# FMC.net
KiCad netlist of a schematic drawn in Altium Designer
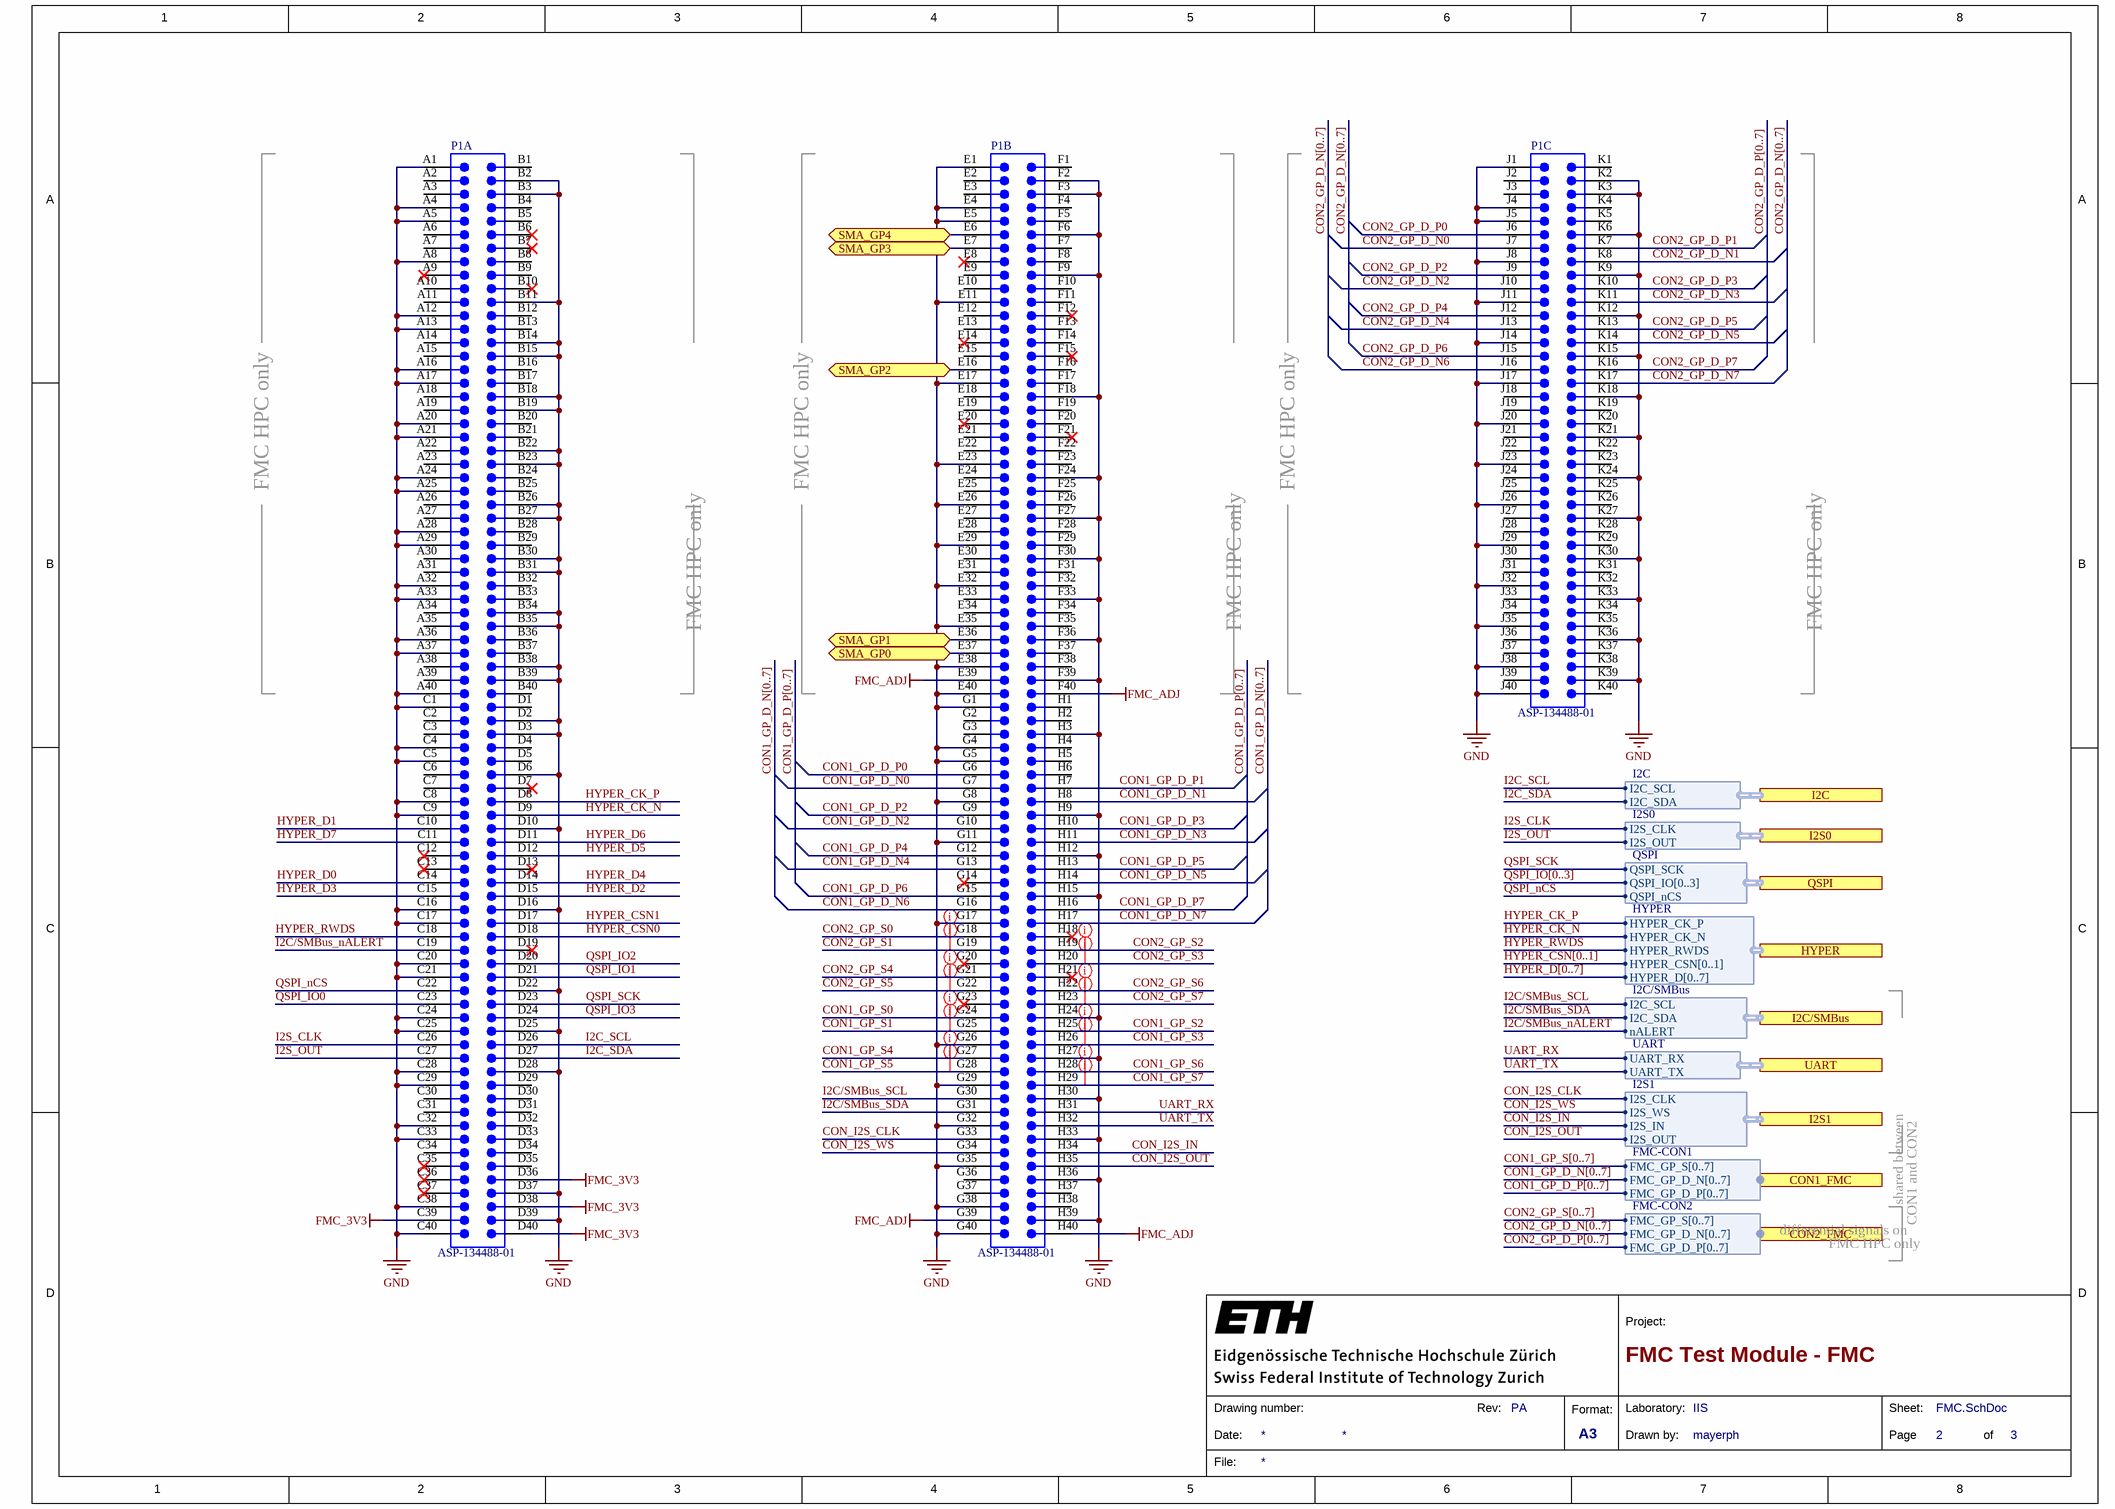
[diagram p0: FMC.SchDoc]

(export (version "E")
  (design (tool "Eeschema 10.0.6"))
  (components
    (comp (ref "P1")
      (value "ASP-134488-01")
      (footprint "BTB-SM1-27-2V400M")
      (description "Board-to-Board Connector, Vertical, 10-Row, Pitch 1.27mm, 400-Position")
      (fields (field (name "MANUFACTURER") "Samtec") (field (name "PUBLISHER") "Altium"))
      (libsource (lib "Altium Content Vault") (part "CN-2P-2M-R400"))
    )
  )
  (nets
    (net (code "11") (name "/CON1_GP_D_N0") (class "Default")
      (node (ref "P1") (pin "G7") (pinfunction "G7_G7") (pintype "passive"))
    )
    (net (code "12") (name "/CON1_GP_D_N1") (class "Default")
      (node (ref "P1") (pin "H8") (pinfunction "H8_H8") (pintype "passive"))
    )
    (net (code "13") (name "/CON1_GP_D_N2") (class "Default")
      (node (ref "P1") (pin "G10") (pinfunction "G10_G10") (pintype "passive"))
    )
    (net (code "14") (name "/CON1_GP_D_N3") (class "Default")
      (node (ref "P1") (pin "H11") (pinfunction "H11_H11") (pintype "passive"))
    )
    (net (code "15") (name "/CON1_GP_D_N4") (class "Default")
      (node (ref "P1") (pin "G13") (pinfunction "G13_G13") (pintype "passive"))
    )
    (net (code "16") (name "/CON1_GP_D_N5") (class "Default")
      (node (ref "P1") (pin "H14") (pinfunction "H14_H14") (pintype "passive"))
    )
    (net (code "17") (name "/CON1_GP_D_N6") (class "Default")
      (node (ref "P1") (pin "G16") (pinfunction "G16_G16") (pintype "passive"))
    )
    (net (code "18") (name "/CON1_GP_D_N7") (class "Default")
      (node (ref "P1") (pin "H17") (pinfunction "H17_H17") (pintype "passive"))
    )
    (net (code "20") (name "/CON1_GP_D_P0") (class "Default")
      (node (ref "P1") (pin "G6") (pinfunction "G6_G6") (pintype "passive"))
    )
    (net (code "21") (name "/CON1_GP_D_P1") (class "Default")
      (node (ref "P1") (pin "H7") (pinfunction "H7_H7") (pintype "passive"))
    )
    (net (code "22") (name "/CON1_GP_D_P2") (class "Default")
      (node (ref "P1") (pin "G9") (pinfunction "G9_G9") (pintype "passive"))
    )
    (net (code "23") (name "/CON1_GP_D_P3") (class "Default")
      (node (ref "P1") (pin "H10") (pinfunction "H10_H10") (pintype "passive"))
    )
    (net (code "24") (name "/CON1_GP_D_P4") (class "Default")
      (node (ref "P1") (pin "G12") (pinfunction "G12_G12") (pintype "passive"))
    )
    (net (code "25") (name "/CON1_GP_D_P5") (class "Default")
      (node (ref "P1") (pin "H13") (pinfunction "H13_H13") (pintype "passive"))
    )
    (net (code "26") (name "/CON1_GP_D_P6") (class "Default")
      (node (ref "P1") (pin "G15") (pinfunction "G15_G15") (pintype "passive"))
    )
    (net (code "27") (name "/CON1_GP_D_P7") (class "Default")
      (node (ref "P1") (pin "H16") (pinfunction "H16_H16") (pintype "passive"))
    )
    (net (code "29") (name "/CON1_GP_S0") (class "Default")
      (node (ref "P1") (pin "G24") (pinfunction "G24_G24") (pintype "passive"))
    )
    (net (code "30") (name "/CON1_GP_S1") (class "Default")
      (node (ref "P1") (pin "G25") (pinfunction "G25_G25") (pintype "passive"))
    )
    (net (code "31") (name "/CON1_GP_S2") (class "Default")
      (node (ref "P1") (pin "H25") (pinfunction "H25_H25") (pintype "passive"))
    )
    (net (code "32") (name "/CON1_GP_S3") (class "Default")
      (node (ref "P1") (pin "H26") (pinfunction "H26_H26") (pintype "passive"))
    )
    (net (code "33") (name "/CON1_GP_S4") (class "Default")
      (node (ref "P1") (pin "G27") (pinfunction "G27_G27") (pintype "passive"))
    )
    (net (code "34") (name "/CON1_GP_S5") (class "Default")
      (node (ref "P1") (pin "G28") (pinfunction "G28_G28") (pintype "passive"))
    )
    (net (code "35") (name "/CON1_GP_S6") (class "Default")
      (node (ref "P1") (pin "H28") (pinfunction "H28_H28") (pintype "passive"))
    )
    (net (code "36") (name "/CON1_GP_S7") (class "Default")
      (node (ref "P1") (pin "H29") (pinfunction "H29_H29") (pintype "passive"))
    )
    (net (code "39") (name "/CON2_GP_D_N0") (class "Default")
      (node (ref "P1") (pin "J7") (pinfunction "J7_J7") (pintype "passive"))
    )
    (net (code "40") (name "/CON2_GP_D_N1") (class "Default")
      (node (ref "P1") (pin "K8") (pinfunction "K8_K8") (pintype "passive"))
    )
    (net (code "41") (name "/CON2_GP_D_N2") (class "Default")
      (node (ref "P1") (pin "J10") (pinfunction "J10_J10") (pintype "passive"))
    )
    (net (code "42") (name "/CON2_GP_D_N3") (class "Default")
      (node (ref "P1") (pin "K11") (pinfunction "K11_K11") (pintype "passive"))
    )
    (net (code "43") (name "/CON2_GP_D_N4") (class "Default")
      (node (ref "P1") (pin "J13") (pinfunction "J13_J13") (pintype "passive"))
    )
    (net (code "44") (name "/CON2_GP_D_N5") (class "Default")
      (node (ref "P1") (pin "K14") (pinfunction "K14_K14") (pintype "passive"))
    )
    (net (code "45") (name "/CON2_GP_D_N6") (class "Default")
      (node (ref "P1") (pin "J16") (pinfunction "J16_J16") (pintype "passive"))
    )
    (net (code "46") (name "/CON2_GP_D_N7") (class "Default")
      (node (ref "P1") (pin "K17") (pinfunction "K17_K17") (pintype "passive"))
    )
    (net (code "48") (name "/CON2_GP_D_P0") (class "Default")
      (node (ref "P1") (pin "J6") (pinfunction "J6_J6") (pintype "passive"))
    )
    (net (code "49") (name "/CON2_GP_D_P1") (class "Default")
      (node (ref "P1") (pin "K7") (pinfunction "K7_K7") (pintype "passive"))
    )
    (net (code "50") (name "/CON2_GP_D_P2") (class "Default")
      (node (ref "P1") (pin "J9") (pinfunction "J9_J9") (pintype "passive"))
    )
    (net (code "51") (name "/CON2_GP_D_P3") (class "Default")
      (node (ref "P1") (pin "K10") (pinfunction "K10_K10") (pintype "passive"))
    )
    (net (code "52") (name "/CON2_GP_D_P4") (class "Default")
      (node (ref "P1") (pin "J12") (pinfunction "J12_J12") (pintype "passive"))
    )
    (net (code "53") (name "/CON2_GP_D_P5") (class "Default")
      (node (ref "P1") (pin "K13") (pinfunction "K13_K13") (pintype "passive"))
    )
    (net (code "54") (name "/CON2_GP_D_P6") (class "Default")
      (node (ref "P1") (pin "J15") (pinfunction "J15_J15") (pintype "passive"))
    )
    (net (code "55") (name "/CON2_GP_D_P7") (class "Default")
      (node (ref "P1") (pin "K16") (pinfunction "K16_K16") (pintype "passive"))
    )
    (net (code "57") (name "/CON2_GP_S0") (class "Default")
      (node (ref "P1") (pin "G18") (pinfunction "G18_G18") (pintype "passive"))
    )
    (net (code "58") (name "/CON2_GP_S1") (class "Default")
      (node (ref "P1") (pin "G19") (pinfunction "G19_G19") (pintype "passive"))
    )
    (net (code "59") (name "/CON2_GP_S2") (class "Default")
      (node (ref "P1") (pin "H19") (pinfunction "H19_H19") (pintype "passive"))
    )
    (net (code "60") (name "/CON2_GP_S3") (class "Default")
      (node (ref "P1") (pin "H20") (pinfunction "H20_H20") (pintype "passive"))
    )
    (net (code "61") (name "/CON2_GP_S4") (class "Default")
      (node (ref "P1") (pin "G21") (pinfunction "G21_G21") (pintype "passive"))
    )
    (net (code "62") (name "/CON2_GP_S5") (class "Default")
      (node (ref "P1") (pin "G22") (pinfunction "G22_G22") (pintype "passive"))
    )
    (net (code "63") (name "/CON2_GP_S6") (class "Default")
      (node (ref "P1") (pin "H22") (pinfunction "H22_H22") (pintype "passive"))
    )
    (net (code "64") (name "/CON2_GP_S7") (class "Default")
      (node (ref "P1") (pin "H23") (pinfunction "H23_H23") (pintype "passive"))
    )
    (net (code "66") (name "/CON_I2S_CLK") (class "Default")
      (node (ref "P1") (pin "G33") (pinfunction "G33_G33") (pintype "passive"))
    )
    (net (code "67") (name "/CON_I2S_IN") (class "Default")
      (node (ref "P1") (pin "H34") (pinfunction "H34_H34") (pintype "passive"))
    )
    (net (code "68") (name "/CON_I2S_OUT") (class "Default")
      (node (ref "P1") (pin "H35") (pinfunction "H35_H35") (pintype "passive"))
    )
    (net (code "69") (name "/CON_I2S_WS") (class "Default")
      (node (ref "P1") (pin "G34") (pinfunction "G34_G34") (pintype "passive"))
    )
    (net (code "70") (name "/HYPER_CK_N") (class "Default")
      (node (ref "P1") (pin "D9") (pinfunction "D9_D9") (pintype "passive"))
    )
    (net (code "71") (name "/HYPER_CK_P") (class "Default")
      (node (ref "P1") (pin "D8") (pinfunction "D8_D8") (pintype "passive"))
    )
    (net (code "72") (name "/HYPER_CSN0") (class "Default")
      (node (ref "P1") (pin "D18") (pinfunction "D18_D18") (pintype "passive"))
    )
    (net (code "73") (name "/HYPER_CSN1") (class "Default")
      (node (ref "P1") (pin "D17") (pinfunction "D17_D17") (pintype "passive"))
    )
    (net (code "75") (name "/HYPER_D0") (class "Default")
      (node (ref "P1") (pin "C14") (pinfunction "C14_C14") (pintype "passive"))
    )
    (net (code "76") (name "/HYPER_D1") (class "Default")
      (node (ref "P1") (pin "C10") (pinfunction "C10_C10") (pintype "passive"))
    )
    (net (code "77") (name "/HYPER_D2") (class "Default")
      (node (ref "P1") (pin "D15") (pinfunction "D15_D15") (pintype "passive"))
    )
    (net (code "78") (name "/HYPER_D3") (class "Default")
      (node (ref "P1") (pin "C15") (pinfunction "C15_C15") (pintype "passive"))
    )
    (net (code "79") (name "/HYPER_D4") (class "Default")
      (node (ref "P1") (pin "D14") (pinfunction "D14_D14") (pintype "passive"))
    )
    (net (code "80") (name "/HYPER_D5") (class "Default")
      (node (ref "P1") (pin "D12") (pinfunction "D12_D12") (pintype "passive"))
    )
    (net (code "81") (name "/HYPER_D6") (class "Default")
      (node (ref "P1") (pin "D11") (pinfunction "D11_D11") (pintype "passive"))
    )
    (net (code "82") (name "/HYPER_D7") (class "Default")
      (node (ref "P1") (pin "C11") (pinfunction "C11_C11") (pintype "passive"))
    )
    (net (code "84") (name "/HYPER_RWDS") (class "Default")
      (node (ref "P1") (pin "C18") (pinfunction "C18_C18") (pintype "passive"))
    )
    (net (code "85") (name "/I2C_SCL") (class "Default")
      (node (ref "P1") (pin "D26") (pinfunction "D26_D26") (pintype "passive"))
    )
    (net (code "86") (name "/I2C_SDA") (class "Default")
      (node (ref "P1") (pin "D27") (pinfunction "D27_D27") (pintype "passive"))
    )
    (net (code "87") (name "/I2C{slash}SMBus_SCL") (class "Default")
      (node (ref "P1") (pin "G30") (pinfunction "G30_G30") (pintype "passive"))
    )
    (net (code "88") (name "/I2C{slash}SMBus_SDA") (class "Default")
      (node (ref "P1") (pin "G31") (pinfunction "G31_G31") (pintype "passive"))
    )
    (net (code "89") (name "/I2C{slash}SMBus_nALERT") (class "Default")
      (node (ref "P1") (pin "C19") (pinfunction "C19_C19") (pintype "passive"))
    )
    (net (code "90") (name "/I2S_CLK") (class "Default")
      (node (ref "P1") (pin "C26") (pinfunction "C26_C26") (pintype "passive"))
    )
    (net (code "91") (name "/I2S_OUT") (class "Default")
      (node (ref "P1") (pin "C27") (pinfunction "C27_C27") (pintype "passive"))
    )
    (net (code "92") (name "/QSPI_IO0") (class "Default")
      (node (ref "P1") (pin "C23") (pinfunction "C23_C23") (pintype "passive"))
    )
    (net (code "93") (name "/QSPI_IO1") (class "Default")
      (node (ref "P1") (pin "D21") (pinfunction "D21_D21") (pintype "passive"))
    )
    (net (code "94") (name "/QSPI_IO2") (class "Default")
      (node (ref "P1") (pin "D20") (pinfunction "D20_D20") (pintype "passive"))
    )
    (net (code "95") (name "/QSPI_IO3") (class "Default")
      (node (ref "P1") (pin "D24") (pinfunction "D24_D24") (pintype "passive"))
    )
    (net (code "97") (name "/QSPI_SCK") (class "Default")
      (node (ref "P1") (pin "D23") (pinfunction "D23_D23") (pintype "passive"))
    )
    (net (code "98") (name "/QSPI_nCS") (class "Default")
      (node (ref "P1") (pin "C22") (pinfunction "C22_C22") (pintype "passive"))
    )
    (net (code "99") (name "/SMA_GP0") (class "Default")
      (node (ref "P1") (pin "E37") (pinfunction "E37_E37") (pintype "passive"))
    )
    (net (code "100") (name "/SMA_GP1") (class "Default")
      (node (ref "P1") (pin "E36") (pinfunction "E36_E36") (pintype "passive"))
    )
    (net (code "101") (name "/SMA_GP2") (class "Default")
      (node (ref "P1") (pin "E16") (pinfunction "E16_E16") (pintype "passive"))
    )
    (net (code "102") (name "/SMA_GP3") (class "Default")
      (node (ref "P1") (pin "E7") (pinfunction "E7_E7") (pintype "passive"))
    )
    (net (code "103") (name "/SMA_GP4") (class "Default")
      (node (ref "P1") (pin "E6") (pinfunction "E6_E6") (pintype "passive"))
    )
    (net (code "104") (name "/UART_RX") (class "Default")
      (node (ref "P1") (pin "H31") (pinfunction "H31_H31") (pintype "passive"))
    )
    (net (code "105") (name "/UART_TX") (class "Default")
      (node (ref "P1") (pin "H32") (pinfunction "H32_H32") (pintype "passive"))
    )
    (net (code "113") (name "FMC_3V3") (class "Default")
      (node (ref "P1") (pin "C39") (pinfunction "C39_C39") (pintype "passive"))
      (node (ref "P1") (pin "D36") (pinfunction "D36_D36") (pintype "passive"))
      (node (ref "P1") (pin "D38") (pinfunction "D38_D38") (pintype "passive"))
      (node (ref "P1") (pin "D40") (pinfunction "D40_D40") (pintype "passive"))
    )
    (net (code "114") (name "FMC_ADJ") (class "Default")
      (node (ref "P1") (pin "E39") (pinfunction "E39_E39") (pintype "passive"))
      (node (ref "P1") (pin "F40") (pinfunction "F40_F40") (pintype "passive"))
      (node (ref "P1") (pin "G39") (pinfunction "G39_G39") (pintype "passive"))
      (node (ref "P1") (pin "H40") (pinfunction "H40_H40") (pintype "passive"))
    )
    (net (code "115") (name "GND") (class "Default")
      (node (ref "P1") (pin "A1") (pinfunction "A1_A1") (pintype "passive"))
      (node (ref "P1") (pin "A12") (pinfunction "A12_A12") (pintype "passive"))
      (node (ref "P1") (pin "A13") (pinfunction "A13_A13") (pintype "passive"))
      (node (ref "P1") (pin "A16") (pinfunction "A16_A16") (pintype "passive"))
      (node (ref "P1") (pin "A17") (pinfunction "A17_A17") (pintype "passive"))
      (node (ref "P1") (pin "A20") (pinfunction "A20_A20") (pintype "passive"))
      (node (ref "P1") (pin "A21") (pinfunction "A21_A21") (pintype "passive"))
      (node (ref "P1") (pin "A24") (pinfunction "A24_A24") (pintype "passive"))
      (node (ref "P1") (pin "A25") (pinfunction "A25_A25") (pintype "passive"))
      (node (ref "P1") (pin "A28") (pinfunction "A28_A28") (pintype "passive"))
      (node (ref "P1") (pin "A29") (pinfunction "A29_A29") (pintype "passive"))
      (node (ref "P1") (pin "A32") (pinfunction "A32_A32") (pintype "passive"))
      (node (ref "P1") (pin "A33") (pinfunction "A33_A33") (pintype "passive"))
      (node (ref "P1") (pin "A36") (pinfunction "A36_A36") (pintype "passive"))
      (node (ref "P1") (pin "A37") (pinfunction "A37_A37") (pintype "passive"))
      (node (ref "P1") (pin "A4") (pinfunction "A4_A4") (pintype "passive"))
      (node (ref "P1") (pin "A40") (pinfunction "A40_A40") (pintype "passive"))
      (node (ref "P1") (pin "A5") (pinfunction "A5_A5") (pintype "passive"))
      (node (ref "P1") (pin "A8") (pinfunction "A8_A8") (pintype "passive"))
      (node (ref "P1") (pin "B11") (pinfunction "B11_B11") (pintype "passive"))
      (node (ref "P1") (pin "B14") (pinfunction "B14_B14") (pintype "passive"))
      (node (ref "P1") (pin "B15") (pinfunction "B15_B15") (pintype "passive"))
      (node (ref "P1") (pin "B18") (pinfunction "B18_B18") (pintype "passive"))
      (node (ref "P1") (pin "B19") (pinfunction "B19_B19") (pintype "passive"))
      (node (ref "P1") (pin "B2") (pinfunction "B2_B2") (pintype "passive"))
      (node (ref "P1") (pin "B22") (pinfunction "B22_B22") (pintype "passive"))
      (node (ref "P1") (pin "B23") (pinfunction "B23_B23") (pintype "passive"))
      (node (ref "P1") (pin "B26") (pinfunction "B26_B26") (pintype "passive"))
      (node (ref "P1") (pin "B27") (pinfunction "B27_B27") (pintype "passive"))
      (node (ref "P1") (pin "B3") (pinfunction "B3_B3") (pintype "passive"))
      (node (ref "P1") (pin "B30") (pinfunction "B30_B30") (pintype "passive"))
      (node (ref "P1") (pin "B31") (pinfunction "B31_B31") (pintype "passive"))
      (node (ref "P1") (pin "B34") (pinfunction "B34_B34") (pintype "passive"))
      (node (ref "P1") (pin "B35") (pinfunction "B35_B35") (pintype "passive"))
      (node (ref "P1") (pin "B38") (pinfunction "B38_B38") (pintype "passive"))
      (node (ref "P1") (pin "B39") (pinfunction "B39_B39") (pintype "passive"))
      (node (ref "P1") (pin "C1") (pinfunction "C1_C1") (pintype "passive"))
      (node (ref "P1") (pin "C16") (pinfunction "C16_C16") (pintype "passive"))
      (node (ref "P1") (pin "C17") (pinfunction "C17_C17") (pintype "passive"))
      (node (ref "P1") (pin "C20") (pinfunction "C20_C20") (pintype "passive"))
      (node (ref "P1") (pin "C21") (pinfunction "C21_C21") (pintype "passive"))
      (node (ref "P1") (pin "C24") (pinfunction "C24_C24") (pintype "passive"))
      (node (ref "P1") (pin "C25") (pinfunction "C25_C25") (pintype "passive"))
      (node (ref "P1") (pin "C28") (pinfunction "C28_C28") (pintype "passive"))
      (node (ref "P1") (pin "C29") (pinfunction "C29_C29") (pintype "passive"))
      (node (ref "P1") (pin "C32") (pinfunction "C32_C32") (pintype "passive"))
      (node (ref "P1") (pin "C33") (pinfunction "C33_C33") (pintype "passive"))
      (node (ref "P1") (pin "C38") (pinfunction "C38_C38") (pintype "passive"))
      (node (ref "P1") (pin "C4") (pinfunction "C4_C4") (pintype "passive"))
      (node (ref "P1") (pin "C40") (pinfunction "C40_C40") (pintype "passive"))
      (node (ref "P1") (pin "C5") (pinfunction "C5_C5") (pintype "passive"))
      (node (ref "P1") (pin "C8") (pinfunction "C8_C8") (pintype "passive"))
      (node (ref "P1") (pin "C9") (pinfunction "C9_C9") (pintype "passive"))
      (node (ref "P1") (pin "D10") (pinfunction "D10_D10") (pintype "passive"))
      (node (ref "P1") (pin "D16") (pinfunction "D16_D16") (pintype "passive"))
      (node (ref "P1") (pin "D2") (pinfunction "D2_D2") (pintype "passive"))
      (node (ref "P1") (pin "D22") (pinfunction "D22_D22") (pintype "passive"))
      (node (ref "P1") (pin "D25") (pinfunction "D25_D25") (pintype "passive"))
      (node (ref "P1") (pin "D28") (pinfunction "D28_D28") (pintype "passive"))
      (node (ref "P1") (pin "D3") (pinfunction "D3_D3") (pintype "passive"))
      (node (ref "P1") (pin "D37") (pinfunction "D37_D37") (pintype "passive"))
      (node (ref "P1") (pin "D39") (pinfunction "D39_D39") (pintype "passive"))
      (node (ref "P1") (pin "D6") (pinfunction "D6_D6") (pintype "passive"))
      (node (ref "P1") (pin "E1") (pinfunction "E1_E1") (pintype "passive"))
      (node (ref "P1") (pin "E11") (pinfunction "E11_E11") (pintype "passive"))
      (node (ref "P1") (pin "E17") (pinfunction "E17_E17") (pintype "passive"))
      (node (ref "P1") (pin "E23") (pinfunction "E23_E23") (pintype "passive"))
      (node (ref "P1") (pin "E26") (pinfunction "E26_E26") (pintype "passive"))
      (node (ref "P1") (pin "E29") (pinfunction "E29_E29") (pintype "passive"))
      (node (ref "P1") (pin "E32") (pinfunction "E32_E32") (pintype "passive"))
      (node (ref "P1") (pin "E35") (pinfunction "E35_E35") (pintype "passive"))
      (node (ref "P1") (pin "E38") (pinfunction "E38_E38") (pintype "passive"))
      (node (ref "P1") (pin "E4") (pinfunction "E4_E4") (pintype "passive"))
      (node (ref "P1") (pin "E40") (pinfunction "E40_E40") (pintype "passive"))
      (node (ref "P1") (pin "E5") (pinfunction "E5_E5") (pintype "passive"))
      (node (ref "P1") (pin "F18") (pinfunction "F18_F18") (pintype "passive"))
      (node (ref "P1") (pin "F2") (pinfunction "F2_F2") (pintype "passive"))
      (node (ref "P1") (pin "F24") (pinfunction "F24_F24") (pintype "passive"))
      (node (ref "P1") (pin "F27") (pinfunction "F27_F27") (pintype "passive"))
      (node (ref "P1") (pin "F3") (pinfunction "F3_F3") (pintype "passive"))
      (node (ref "P1") (pin "F30") (pinfunction "F30_F30") (pintype "passive"))
      (node (ref "P1") (pin "F33") (pinfunction "F33_F33") (pintype "passive"))
      (node (ref "P1") (pin "F36") (pinfunction "F36_F36") (pintype "passive"))
      (node (ref "P1") (pin "F39") (pinfunction "F39_F39") (pintype "passive"))
      (node (ref "P1") (pin "F6") (pinfunction "F6_F6") (pintype "passive"))
      (node (ref "P1") (pin "F9") (pinfunction "F9_F9") (pintype "passive"))
      (node (ref "P1") (pin "G1") (pinfunction "G1_G1") (pintype "passive"))
      (node (ref "P1") (pin "G11") (pinfunction "G11_G11") (pintype "passive"))
      (node (ref "P1") (pin "G17") (pinfunction "G17_G17") (pintype "passive"))
      (node (ref "P1") (pin "G26") (pinfunction "G26_G26") (pintype "passive"))
      (node (ref "P1") (pin "G29") (pinfunction "G29_G29") (pintype "passive"))
      (node (ref "P1") (pin "G32") (pinfunction "G32_G32") (pintype "passive"))
      (node (ref "P1") (pin "G35") (pinfunction "G35_G35") (pintype "passive"))
      (node (ref "P1") (pin "G38") (pinfunction "G38_G38") (pintype "passive"))
      (node (ref "P1") (pin "G4") (pinfunction "G4_G4") (pintype "passive"))
      (node (ref "P1") (pin "G40") (pinfunction "G40_G40") (pintype "passive"))
      (node (ref "P1") (pin "G5") (pinfunction "G5_G5") (pintype "passive"))
      (node (ref "P1") (pin "G8") (pinfunction "G8_G8") (pintype "passive"))
      (node (ref "P1") (pin "H12") (pinfunction "H12_H12") (pintype "passive"))
      (node (ref "P1") (pin "H15") (pinfunction "H15_H15") (pintype "passive"))
      (node (ref "P1") (pin "H24") (pinfunction "H24_H24") (pintype "passive"))
      (node (ref "P1") (pin "H27") (pinfunction "H27_H27") (pintype "passive"))
      (node (ref "P1") (pin "H3") (pinfunction "H3_H3") (pintype "passive"))
      (node (ref "P1") (pin "H30") (pinfunction "H30_H30") (pintype "passive"))
      (node (ref "P1") (pin "H33") (pinfunction "H33_H33") (pintype "passive"))
      (node (ref "P1") (pin "H36") (pinfunction "H36_H36") (pintype "passive"))
      (node (ref "P1") (pin "H39") (pinfunction "H39_H39") (pintype "passive"))
      (node (ref "P1") (pin "H9") (pinfunction "H9_H9") (pintype "passive"))
      (node (ref "P1") (pin "J1") (pinfunction "J1_J1") (pintype "passive"))
      (node (ref "P1") (pin "J11") (pinfunction "J11_J11") (pintype "passive"))
      (node (ref "P1") (pin "J14") (pinfunction "J14_J14") (pintype "passive"))
      (node (ref "P1") (pin "J17") (pinfunction "J17_J17") (pintype "passive"))
      (node (ref "P1") (pin "J20") (pinfunction "J20_J20") (pintype "passive"))
      (node (ref "P1") (pin "J23") (pinfunction "J23_J23") (pintype "passive"))
      (node (ref "P1") (pin "J26") (pinfunction "J26_J26") (pintype "passive"))
      (node (ref "P1") (pin "J29") (pinfunction "J29_J29") (pintype "passive"))
      (node (ref "P1") (pin "J32") (pinfunction "J32_J32") (pintype "passive"))
      (node (ref "P1") (pin "J35") (pinfunction "J35_J35") (pintype "passive"))
      (node (ref "P1") (pin "J38") (pinfunction "J38_J38") (pintype "passive"))
      (node (ref "P1") (pin "J4") (pinfunction "J4_J4") (pintype "passive"))
      (node (ref "P1") (pin "J40") (pinfunction "J40_J40") (pintype "passive"))
      (node (ref "P1") (pin "J5") (pinfunction "J5_J5") (pintype "passive"))
      (node (ref "P1") (pin "J8") (pinfunction "J8_J8") (pintype "passive"))
      (node (ref "P1") (pin "K12") (pinfunction "K12_K12") (pintype "passive"))
      (node (ref "P1") (pin "K15") (pinfunction "K15_K15") (pintype "passive"))
      (node (ref "P1") (pin "K18") (pinfunction "K18_K18") (pintype "passive"))
      (node (ref "P1") (pin "K2") (pinfunction "K2_K2") (pintype "passive"))
      (node (ref "P1") (pin "K21") (pinfunction "K21_K21") (pintype "passive"))
      (node (ref "P1") (pin "K24") (pinfunction "K24_K24") (pintype "passive"))
      (node (ref "P1") (pin "K27") (pinfunction "K27_K27") (pintype "passive"))
      (node (ref "P1") (pin "K3") (pinfunction "K3_K3") (pintype "passive"))
      (node (ref "P1") (pin "K30") (pinfunction "K30_K30") (pintype "passive"))
      (node (ref "P1") (pin "K33") (pinfunction "K33_K33") (pintype "passive"))
      (node (ref "P1") (pin "K36") (pinfunction "K36_K36") (pintype "passive"))
      (node (ref "P1") (pin "K39") (pinfunction "K39_K39") (pintype "passive"))
      (node (ref "P1") (pin "K6") (pinfunction "K6_K6") (pintype "passive"))
      (node (ref "P1") (pin "K9") (pinfunction "K9_K9") (pintype "passive"))
    )
    (net (code "116") (name "unconnected-(P1-PadA2)") (class "Default")
      (node (ref "P1") (pin "A2") (pinfunction "A2_A2") (pintype "passive"))
    )
    (net (code "117") (name "unconnected-(P1-PadA3)") (class "Default")
      (node (ref "P1") (pin "A3") (pinfunction "A3_A3") (pintype "passive"))
    )
    (net (code "118") (name "unconnected-(P1-PadA6)") (class "Default")
      (node (ref "P1") (pin "A6") (pinfunction "A6_A6") (pintype "passive"))
    )
    (net (code "119") (name "unconnected-(P1-PadA7)") (class "Default")
      (node (ref "P1") (pin "A7") (pinfunction "A7_A7") (pintype "passive"))
    )
    (net (code "120") (name "unconnected-(P1-PadA9)") (class "Default")
      (node (ref "P1") (pin "A9") (pinfunction "A9_A9") (pintype "passive+no_connect"))
    )
    (net (code "121") (name "unconnected-(P1-PadA10)") (class "Default")
      (node (ref "P1") (pin "A10") (pinfunction "A10_A10") (pintype "passive"))
    )
    (net (code "122") (name "unconnected-(P1-PadA11)") (class "Default")
      (node (ref "P1") (pin "A11") (pinfunction "A11_A11") (pintype "passive"))
    )
    (net (code "123") (name "unconnected-(P1-PadA14)") (class "Default")
      (node (ref "P1") (pin "A14") (pinfunction "A14_A14") (pintype "passive"))
    )
    (net (code "124") (name "unconnected-(P1-PadA15)") (class "Default")
      (node (ref "P1") (pin "A15") (pinfunction "A15_A15") (pintype "passive"))
    )
    (net (code "125") (name "unconnected-(P1-PadA18)") (class "Default")
      (node (ref "P1") (pin "A18") (pinfunction "A18_A18") (pintype "passive"))
    )
    (net (code "126") (name "unconnected-(P1-PadA19)") (class "Default")
      (node (ref "P1") (pin "A19") (pinfunction "A19_A19") (pintype "passive"))
    )
    (net (code "127") (name "unconnected-(P1-PadA22)") (class "Default")
      (node (ref "P1") (pin "A22") (pinfunction "A22_A22") (pintype "passive"))
    )
    (net (code "128") (name "unconnected-(P1-PadA23)") (class "Default")
      (node (ref "P1") (pin "A23") (pinfunction "A23_A23") (pintype "passive"))
    )
    (net (code "129") (name "unconnected-(P1-PadA26)") (class "Default")
      (node (ref "P1") (pin "A26") (pinfunction "A26_A26") (pintype "passive"))
    )
    (net (code "130") (name "unconnected-(P1-PadA27)") (class "Default")
      (node (ref "P1") (pin "A27") (pinfunction "A27_A27") (pintype "passive"))
    )
    (net (code "131") (name "unconnected-(P1-PadA30)") (class "Default")
      (node (ref "P1") (pin "A30") (pinfunction "A30_A30") (pintype "passive"))
    )
    (net (code "132") (name "unconnected-(P1-PadA31)") (class "Default")
      (node (ref "P1") (pin "A31") (pinfunction "A31_A31") (pintype "passive"))
    )
    (net (code "133") (name "unconnected-(P1-PadA34)") (class "Default")
      (node (ref "P1") (pin "A34") (pinfunction "A34_A34") (pintype "passive"))
    )
    (net (code "134") (name "unconnected-(P1-PadA35)") (class "Default")
      (node (ref "P1") (pin "A35") (pinfunction "A35_A35") (pintype "passive"))
    )
    (net (code "135") (name "unconnected-(P1-PadA38)") (class "Default")
      (node (ref "P1") (pin "A38") (pinfunction "A38_A38") (pintype "passive"))
    )
    (net (code "136") (name "unconnected-(P1-PadA39)") (class "Default")
      (node (ref "P1") (pin "A39") (pinfunction "A39_A39") (pintype "passive"))
    )
    (net (code "137") (name "unconnected-(P1-PadB1)") (class "Default")
      (node (ref "P1") (pin "B1") (pinfunction "B1_B1") (pintype "passive"))
    )
    (net (code "138") (name "unconnected-(P1-PadB4)") (class "Default")
      (node (ref "P1") (pin "B4") (pinfunction "B4_B4") (pintype "passive"))
    )
    (net (code "139") (name "unconnected-(P1-PadB5)") (class "Default")
      (node (ref "P1") (pin "B5") (pinfunction "B5_B5") (pintype "passive"))
    )
    (net (code "140") (name "unconnected-(P1-PadB6)") (class "Default")
      (node (ref "P1") (pin "B6") (pinfunction "B6_B6") (pintype "passive+no_connect"))
    )
    (net (code "141") (name "unconnected-(P1-PadB7)") (class "Default")
      (node (ref "P1") (pin "B7") (pinfunction "B7_B7") (pintype "passive+no_connect"))
    )
    (net (code "142") (name "unconnected-(P1-PadB8)") (class "Default")
      (node (ref "P1") (pin "B8") (pinfunction "B8_B8") (pintype "passive"))
    )
    (net (code "143") (name "unconnected-(P1-PadB9)") (class "Default")
      (node (ref "P1") (pin "B9") (pinfunction "B9_B9") (pintype "passive"))
    )
    (net (code "144") (name "unconnected-(P1-PadB10)") (class "Default")
      (node (ref "P1") (pin "B10") (pinfunction "B10_B10") (pintype "passive+no_connect"))
    )
    (net (code "145") (name "unconnected-(P1-PadB12)") (class "Default")
      (node (ref "P1") (pin "B12") (pinfunction "B12_B12") (pintype "passive"))
    )
    (net (code "146") (name "unconnected-(P1-PadB13)") (class "Default")
      (node (ref "P1") (pin "B13") (pinfunction "B13_B13") (pintype "passive"))
    )
    (net (code "147") (name "unconnected-(P1-PadB16)") (class "Default")
      (node (ref "P1") (pin "B16") (pinfunction "B16_B16") (pintype "passive"))
    )
    (net (code "148") (name "unconnected-(P1-PadB17)") (class "Default")
      (node (ref "P1") (pin "B17") (pinfunction "B17_B17") (pintype "passive"))
    )
    (net (code "149") (name "unconnected-(P1-PadB20)") (class "Default")
      (node (ref "P1") (pin "B20") (pinfunction "B20_B20") (pintype "passive"))
    )
    (net (code "150") (name "unconnected-(P1-PadB21)") (class "Default")
      (node (ref "P1") (pin "B21") (pinfunction "B21_B21") (pintype "passive"))
    )
    (net (code "151") (name "unconnected-(P1-PadB24)") (class "Default")
      (node (ref "P1") (pin "B24") (pinfunction "B24_B24") (pintype "passive"))
    )
    (net (code "152") (name "unconnected-(P1-PadB25)") (class "Default")
      (node (ref "P1") (pin "B25") (pinfunction "B25_B25") (pintype "passive"))
    )
    (net (code "153") (name "unconnected-(P1-PadB28)") (class "Default")
      (node (ref "P1") (pin "B28") (pinfunction "B28_B28") (pintype "passive"))
    )
    (net (code "154") (name "unconnected-(P1-PadB29)") (class "Default")
      (node (ref "P1") (pin "B29") (pinfunction "B29_B29") (pintype "passive"))
    )
    (net (code "155") (name "unconnected-(P1-PadB32)") (class "Default")
      (node (ref "P1") (pin "B32") (pinfunction "B32_B32") (pintype "passive"))
    )
    (net (code "156") (name "unconnected-(P1-PadB33)") (class "Default")
      (node (ref "P1") (pin "B33") (pinfunction "B33_B33") (pintype "passive"))
    )
    (net (code "157") (name "unconnected-(P1-PadB36)") (class "Default")
      (node (ref "P1") (pin "B36") (pinfunction "B36_B36") (pintype "passive"))
    )
    (net (code "158") (name "unconnected-(P1-PadB37)") (class "Default")
      (node (ref "P1") (pin "B37") (pinfunction "B37_B37") (pintype "passive"))
    )
    (net (code "159") (name "unconnected-(P1-PadB40)") (class "Default")
      (node (ref "P1") (pin "B40") (pinfunction "B40_B40") (pintype "passive"))
    )
    (net (code "160") (name "unconnected-(P1-PadC2)") (class "Default")
      (node (ref "P1") (pin "C2") (pinfunction "C2_C2") (pintype "passive"))
    )
    (net (code "161") (name "unconnected-(P1-PadC3)") (class "Default")
      (node (ref "P1") (pin "C3") (pinfunction "C3_C3") (pintype "passive"))
    )
    (net (code "162") (name "unconnected-(P1-PadC6)") (class "Default")
      (node (ref "P1") (pin "C6") (pinfunction "C6_C6") (pintype "passive"))
    )
    (net (code "163") (name "unconnected-(P1-PadC7)") (class "Default")
      (node (ref "P1") (pin "C7") (pinfunction "C7_C7") (pintype "passive"))
    )
    (net (code "164") (name "unconnected-(P1-PadC12)") (class "Default")
      (node (ref "P1") (pin "C12") (pinfunction "C12_C12") (pintype "passive+no_connect"))
    )
    (net (code "165") (name "unconnected-(P1-PadC13)") (class "Default")
      (node (ref "P1") (pin "C13") (pinfunction "C13_C13") (pintype "passive+no_connect"))
    )
    (net (code "166") (name "unconnected-(P1-PadC30)") (class "Default")
      (node (ref "P1") (pin "C30") (pinfunction "C30_C30") (pintype "passive"))
    )
    (net (code "167") (name "unconnected-(P1-PadC31)") (class "Default")
      (node (ref "P1") (pin "C31") (pinfunction "C31_C31") (pintype "passive"))
    )
    (net (code "168") (name "unconnected-(P1-PadC34)") (class "Default")
      (node (ref "P1") (pin "C34") (pinfunction "C34_C34") (pintype "passive"))
    )
    (net (code "169") (name "unconnected-(P1-PadC35)") (class "Default")
      (node (ref "P1") (pin "C35") (pinfunction "C35_C35") (pintype "passive+no_connect"))
    )
    (net (code "170") (name "unconnected-(P1-PadC36)") (class "Default")
      (node (ref "P1") (pin "C36") (pinfunction "C36_C36") (pintype "passive+no_connect"))
    )
    (net (code "171") (name "unconnected-(P1-PadC37)") (class "Default")
      (node (ref "P1") (pin "C37") (pinfunction "C37_C37") (pintype "passive+no_connect"))
    )
    (net (code "172") (name "unconnected-(P1-PadD1)") (class "Default")
      (node (ref "P1") (pin "D1") (pinfunction "D1_D1") (pintype "passive"))
    )
    (net (code "173") (name "unconnected-(P1-PadD4)") (class "Default")
      (node (ref "P1") (pin "D4") (pinfunction "D4_D4") (pintype "passive"))
    )
    (net (code "174") (name "unconnected-(P1-PadD5)") (class "Default")
      (node (ref "P1") (pin "D5") (pinfunction "D5_D5") (pintype "passive"))
    )
    (net (code "175") (name "unconnected-(P1-PadD7)") (class "Default")
      (node (ref "P1") (pin "D7") (pinfunction "D7_D7") (pintype "passive+no_connect"))
    )
    (net (code "176") (name "unconnected-(P1-PadD13)") (class "Default")
      (node (ref "P1") (pin "D13") (pinfunction "D13_D13") (pintype "passive+no_connect"))
    )
    (net (code "177") (name "unconnected-(P1-PadD19)") (class "Default")
      (node (ref "P1") (pin "D19") (pinfunction "D19_D19") (pintype "passive+no_connect"))
    )
    (net (code "178") (name "unconnected-(P1-PadD29)") (class "Default")
      (node (ref "P1") (pin "D29") (pinfunction "D29_D29") (pintype "passive"))
    )
    (net (code "179") (name "unconnected-(P1-PadD30)") (class "Default")
      (node (ref "P1") (pin "D30") (pinfunction "D30_D30") (pintype "passive"))
    )
    (net (code "180") (name "unconnected-(P1-PadD31)") (class "Default")
      (node (ref "P1") (pin "D31") (pinfunction "D31_D31") (pintype "passive"))
    )
    (net (code "181") (name "unconnected-(P1-PadD32)") (class "Default")
      (node (ref "P1") (pin "D32") (pinfunction "D32_D32") (pintype "passive"))
    )
    (net (code "182") (name "unconnected-(P1-PadD33)") (class "Default")
      (node (ref "P1") (pin "D33") (pinfunction "D33_D33") (pintype "passive"))
    )
    (net (code "183") (name "unconnected-(P1-PadD34)") (class "Default")
      (node (ref "P1") (pin "D34") (pinfunction "D34_D34") (pintype "passive"))
    )
    (net (code "184") (name "unconnected-(P1-PadD35)") (class "Default")
      (node (ref "P1") (pin "D35") (pinfunction "D35_D35") (pintype "passive"))
    )
    (net (code "185") (name "unconnected-(P1-PadE2)") (class "Default")
      (node (ref "P1") (pin "E2") (pinfunction "E2_E2") (pintype "passive"))
    )
    (net (code "186") (name "unconnected-(P1-PadE3)") (class "Default")
      (node (ref "P1") (pin "E3") (pinfunction "E3_E3") (pintype "passive"))
    )
    (net (code "187") (name "unconnected-(P1-PadE8)") (class "Default")
      (node (ref "P1") (pin "E8") (pinfunction "E8_E8") (pintype "passive+no_connect"))
    )
    (net (code "188") (name "unconnected-(P1-PadE9)") (class "Default")
      (node (ref "P1") (pin "E9") (pinfunction "E9_E9") (pintype "passive"))
    )
    (net (code "189") (name "unconnected-(P1-PadE10)") (class "Default")
      (node (ref "P1") (pin "E10") (pinfunction "E10_E10") (pintype "passive"))
    )
    (net (code "190") (name "unconnected-(P1-PadE12)") (class "Default")
      (node (ref "P1") (pin "E12") (pinfunction "E12_E12") (pintype "passive"))
    )
    (net (code "191") (name "unconnected-(P1-PadE13)") (class "Default")
      (node (ref "P1") (pin "E13") (pinfunction "E13_E13") (pintype "passive"))
    )
    (net (code "192") (name "unconnected-(P1-PadE14)") (class "Default")
      (node (ref "P1") (pin "E14") (pinfunction "E14_E14") (pintype "passive+no_connect"))
    )
    (net (code "193") (name "unconnected-(P1-PadE15)") (class "Default")
      (node (ref "P1") (pin "E15") (pinfunction "E15_E15") (pintype "passive"))
    )
    (net (code "194") (name "unconnected-(P1-PadE18)") (class "Default")
      (node (ref "P1") (pin "E18") (pinfunction "E18_E18") (pintype "passive"))
    )
    (net (code "195") (name "unconnected-(P1-PadE19)") (class "Default")
      (node (ref "P1") (pin "E19") (pinfunction "E19_E19") (pintype "passive"))
    )
    (net (code "196") (name "unconnected-(P1-PadE20)") (class "Default")
      (node (ref "P1") (pin "E20") (pinfunction "E20_E20") (pintype "passive+no_connect"))
    )
    (net (code "197") (name "unconnected-(P1-PadE21)") (class "Default")
      (node (ref "P1") (pin "E21") (pinfunction "E21_E21") (pintype "passive"))
    )
    (net (code "198") (name "unconnected-(P1-PadE22)") (class "Default")
      (node (ref "P1") (pin "E22") (pinfunction "E22_E22") (pintype "passive"))
    )
    (net (code "199") (name "unconnected-(P1-PadE24)") (class "Default")
      (node (ref "P1") (pin "E24") (pinfunction "E24_E24") (pintype "passive"))
    )
    (net (code "200") (name "unconnected-(P1-PadE25)") (class "Default")
      (node (ref "P1") (pin "E25") (pinfunction "E25_E25") (pintype "passive"))
    )
    (net (code "201") (name "unconnected-(P1-PadE27)") (class "Default")
      (node (ref "P1") (pin "E27") (pinfunction "E27_E27") (pintype "passive"))
    )
    (net (code "202") (name "unconnected-(P1-PadE28)") (class "Default")
      (node (ref "P1") (pin "E28") (pinfunction "E28_E28") (pintype "passive"))
    )
    (net (code "203") (name "unconnected-(P1-PadE30)") (class "Default")
      (node (ref "P1") (pin "E30") (pinfunction "E30_E30") (pintype "passive"))
    )
    (net (code "204") (name "unconnected-(P1-PadE31)") (class "Default")
      (node (ref "P1") (pin "E31") (pinfunction "E31_E31") (pintype "passive"))
    )
    (net (code "205") (name "unconnected-(P1-PadE33)") (class "Default")
      (node (ref "P1") (pin "E33") (pinfunction "E33_E33") (pintype "passive"))
    )
    (net (code "206") (name "unconnected-(P1-PadE34)") (class "Default")
      (node (ref "P1") (pin "E34") (pinfunction "E34_E34") (pintype "passive"))
    )
    (net (code "207") (name "unconnected-(P1-PadF1)") (class "Default")
      (node (ref "P1") (pin "F1") (pinfunction "F1_F1") (pintype "passive"))
    )
    (net (code "208") (name "unconnected-(P1-PadF4)") (class "Default")
      (node (ref "P1") (pin "F4") (pinfunction "F4_F4") (pintype "passive"))
    )
    (net (code "209") (name "unconnected-(P1-PadF5)") (class "Default")
      (node (ref "P1") (pin "F5") (pinfunction "F5_F5") (pintype "passive"))
    )
    (net (code "210") (name "unconnected-(P1-PadF7)") (class "Default")
      (node (ref "P1") (pin "F7") (pinfunction "F7_F7") (pintype "passive"))
    )
    (net (code "211") (name "unconnected-(P1-PadF8)") (class "Default")
      (node (ref "P1") (pin "F8") (pinfunction "F8_F8") (pintype "passive"))
    )
    (net (code "212") (name "unconnected-(P1-PadF10)") (class "Default")
      (node (ref "P1") (pin "F10") (pinfunction "F10_F10") (pintype "passive"))
    )
    (net (code "213") (name "unconnected-(P1-PadF11)") (class "Default")
      (node (ref "P1") (pin "F11") (pinfunction "F11_F11") (pintype "passive"))
    )
    (net (code "214") (name "unconnected-(P1-PadF12)") (class "Default")
      (node (ref "P1") (pin "F12") (pinfunction "F12_F12") (pintype "passive+no_connect"))
    )
    (net (code "215") (name "unconnected-(P1-PadF13)") (class "Default")
      (node (ref "P1") (pin "F13") (pinfunction "F13_F13") (pintype "passive"))
    )
    (net (code "216") (name "unconnected-(P1-PadF14)") (class "Default")
      (node (ref "P1") (pin "F14") (pinfunction "F14_F14") (pintype "passive"))
    )
    (net (code "217") (name "unconnected-(P1-PadF15)") (class "Default")
      (node (ref "P1") (pin "F15") (pinfunction "F15_F15") (pintype "passive+no_connect"))
    )
    (net (code "218") (name "unconnected-(P1-PadF16)") (class "Default")
      (node (ref "P1") (pin "F16") (pinfunction "F16_F16") (pintype "passive"))
    )
    (net (code "219") (name "unconnected-(P1-PadF17)") (class "Default")
      (node (ref "P1") (pin "F17") (pinfunction "F17_F17") (pintype "passive"))
    )
    (net (code "220") (name "unconnected-(P1-PadF19)") (class "Default")
      (node (ref "P1") (pin "F19") (pinfunction "F19_F19") (pintype "passive"))
    )
    (net (code "221") (name "unconnected-(P1-PadF20)") (class "Default")
      (node (ref "P1") (pin "F20") (pinfunction "F20_F20") (pintype "passive"))
    )
    (net (code "222") (name "unconnected-(P1-PadF21)") (class "Default")
      (node (ref "P1") (pin "F21") (pinfunction "F21_F21") (pintype "passive+no_connect"))
    )
    (net (code "223") (name "unconnected-(P1-PadF22)") (class "Default")
      (node (ref "P1") (pin "F22") (pinfunction "F22_F22") (pintype "passive"))
    )
    (net (code "224") (name "unconnected-(P1-PadF23)") (class "Default")
      (node (ref "P1") (pin "F23") (pinfunction "F23_F23") (pintype "passive"))
    )
    (net (code "225") (name "unconnected-(P1-PadF25)") (class "Default")
      (node (ref "P1") (pin "F25") (pinfunction "F25_F25") (pintype "passive"))
    )
    (net (code "226") (name "unconnected-(P1-PadF26)") (class "Default")
      (node (ref "P1") (pin "F26") (pinfunction "F26_F26") (pintype "passive"))
    )
    (net (code "227") (name "unconnected-(P1-PadF28)") (class "Default")
      (node (ref "P1") (pin "F28") (pinfunction "F28_F28") (pintype "passive"))
    )
    (net (code "228") (name "unconnected-(P1-PadF29)") (class "Default")
      (node (ref "P1") (pin "F29") (pinfunction "F29_F29") (pintype "passive"))
    )
    (net (code "229") (name "unconnected-(P1-PadF31)") (class "Default")
      (node (ref "P1") (pin "F31") (pinfunction "F31_F31") (pintype "passive"))
    )
    (net (code "230") (name "unconnected-(P1-PadF32)") (class "Default")
      (node (ref "P1") (pin "F32") (pinfunction "F32_F32") (pintype "passive"))
    )
    (net (code "231") (name "unconnected-(P1-PadF34)") (class "Default")
      (node (ref "P1") (pin "F34") (pinfunction "F34_F34") (pintype "passive"))
    )
    (net (code "232") (name "unconnected-(P1-PadF35)") (class "Default")
      (node (ref "P1") (pin "F35") (pinfunction "F35_F35") (pintype "passive"))
    )
    (net (code "233") (name "unconnected-(P1-PadF37)") (class "Default")
      (node (ref "P1") (pin "F37") (pinfunction "F37_F37") (pintype "passive"))
    )
    (net (code "234") (name "unconnected-(P1-PadF38)") (class "Default")
      (node (ref "P1") (pin "F38") (pinfunction "F38_F38") (pintype "passive"))
    )
    (net (code "235") (name "unconnected-(P1-PadG2)") (class "Default")
      (node (ref "P1") (pin "G2") (pinfunction "G2_G2") (pintype "passive"))
    )
    (net (code "236") (name "unconnected-(P1-PadG3)") (class "Default")
      (node (ref "P1") (pin "G3") (pinfunction "G3_G3") (pintype "passive"))
    )
    (net (code "237") (name "unconnected-(P1-PadG14)") (class "Default")
      (node (ref "P1") (pin "G14") (pinfunction "G14_G14") (pintype "passive+no_connect"))
    )
    (net (code "238") (name "unconnected-(P1-PadG20)") (class "Default")
      (node (ref "P1") (pin "G20") (pinfunction "G20_G20") (pintype "passive+no_connect"))
    )
    (net (code "239") (name "unconnected-(P1-PadG23)") (class "Default")
      (node (ref "P1") (pin "G23") (pinfunction "G23_G23") (pintype "passive+no_connect"))
    )
    (net (code "240") (name "unconnected-(P1-PadG36)") (class "Default")
      (node (ref "P1") (pin "G36") (pinfunction "G36_G36") (pintype "passive"))
    )
    (net (code "241") (name "unconnected-(P1-PadG37)") (class "Default")
      (node (ref "P1") (pin "G37") (pinfunction "G37_G37") (pintype "passive"))
    )
    (net (code "242") (name "unconnected-(P1-PadH1)") (class "Default")
      (node (ref "P1") (pin "H1") (pinfunction "H1_H1") (pintype "passive"))
    )
    (net (code "243") (name "unconnected-(P1-PadH2)") (class "Default")
      (node (ref "P1") (pin "H2") (pinfunction "H2_H2") (pintype "passive"))
    )
    (net (code "244") (name "unconnected-(P1-PadH4)") (class "Default")
      (node (ref "P1") (pin "H4") (pinfunction "H4_H4") (pintype "passive"))
    )
    (net (code "245") (name "unconnected-(P1-PadH5)") (class "Default")
      (node (ref "P1") (pin "H5") (pinfunction "H5_H5") (pintype "passive"))
    )
    (net (code "246") (name "unconnected-(P1-PadH6)") (class "Default")
      (node (ref "P1") (pin "H6") (pinfunction "H6_H6") (pintype "passive"))
    )
    (net (code "247") (name "unconnected-(P1-PadH18)") (class "Default")
      (node (ref "P1") (pin "H18") (pinfunction "H18_H18") (pintype "passive+no_connect"))
    )
    (net (code "248") (name "unconnected-(P1-PadH21)") (class "Default")
      (node (ref "P1") (pin "H21") (pinfunction "H21_H21") (pintype "passive+no_connect"))
    )
    (net (code "249") (name "unconnected-(P1-PadH37)") (class "Default")
      (node (ref "P1") (pin "H37") (pinfunction "H37_H37") (pintype "passive"))
    )
    (net (code "250") (name "unconnected-(P1-PadH38)") (class "Default")
      (node (ref "P1") (pin "H38") (pinfunction "H38_H38") (pintype "passive"))
    )
    (net (code "251") (name "unconnected-(P1-PadJ2)") (class "Default")
      (node (ref "P1") (pin "J2") (pinfunction "J2_J2") (pintype "passive"))
    )
    (net (code "252") (name "unconnected-(P1-PadJ3)") (class "Default")
      (node (ref "P1") (pin "J3") (pinfunction "J3_J3") (pintype "passive"))
    )
    (net (code "253") (name "unconnected-(P1-PadJ18)") (class "Default")
      (node (ref "P1") (pin "J18") (pinfunction "J18_J18") (pintype "passive"))
    )
    (net (code "254") (name "unconnected-(P1-PadJ19)") (class "Default")
      (node (ref "P1") (pin "J19") (pinfunction "J19_J19") (pintype "passive"))
    )
    (net (code "255") (name "unconnected-(P1-PadJ21)") (class "Default")
      (node (ref "P1") (pin "J21") (pinfunction "J21_J21") (pintype "passive"))
    )
    (net (code "256") (name "unconnected-(P1-PadJ22)") (class "Default")
      (node (ref "P1") (pin "J22") (pinfunction "J22_J22") (pintype "passive"))
    )
    (net (code "257") (name "unconnected-(P1-PadJ24)") (class "Default")
      (node (ref "P1") (pin "J24") (pinfunction "J24_J24") (pintype "passive"))
    )
    (net (code "258") (name "unconnected-(P1-PadJ25)") (class "Default")
      (node (ref "P1") (pin "J25") (pinfunction "J25_J25") (pintype "passive"))
    )
    (net (code "259") (name "unconnected-(P1-PadJ27)") (class "Default")
      (node (ref "P1") (pin "J27") (pinfunction "J27_J27") (pintype "passive"))
    )
    (net (code "260") (name "unconnected-(P1-PadJ28)") (class "Default")
      (node (ref "P1") (pin "J28") (pinfunction "J28_J28") (pintype "passive"))
    )
    (net (code "261") (name "unconnected-(P1-PadJ30)") (class "Default")
      (node (ref "P1") (pin "J30") (pinfunction "J30_J30") (pintype "passive"))
    )
    (net (code "262") (name "unconnected-(P1-PadJ31)") (class "Default")
      (node (ref "P1") (pin "J31") (pinfunction "J31_J31") (pintype "passive"))
    )
    (net (code "263") (name "unconnected-(P1-PadJ33)") (class "Default")
      (node (ref "P1") (pin "J33") (pinfunction "J33_J33") (pintype "passive"))
    )
    (net (code "264") (name "unconnected-(P1-PadJ34)") (class "Default")
      (node (ref "P1") (pin "J34") (pinfunction "J34_J34") (pintype "passive"))
    )
    (net (code "265") (name "unconnected-(P1-PadJ36)") (class "Default")
      (node (ref "P1") (pin "J36") (pinfunction "J36_J36") (pintype "passive"))
    )
    (net (code "266") (name "unconnected-(P1-PadJ37)") (class "Default")
      (node (ref "P1") (pin "J37") (pinfunction "J37_J37") (pintype "passive"))
    )
    (net (code "267") (name "unconnected-(P1-PadJ39)") (class "Default")
      (node (ref "P1") (pin "J39") (pinfunction "J39_J39") (pintype "passive"))
    )
    (net (code "268") (name "unconnected-(P1-PadK1)") (class "Default")
      (node (ref "P1") (pin "K1") (pinfunction "K1_K1") (pintype "passive"))
    )
    (net (code "269") (name "unconnected-(P1-PadK4)") (class "Default")
      (node (ref "P1") (pin "K4") (pinfunction "K4_K4") (pintype "passive"))
    )
    (net (code "270") (name "unconnected-(P1-PadK5)") (class "Default")
      (node (ref "P1") (pin "K5") (pinfunction "K5_K5") (pintype "passive"))
    )
    (net (code "271") (name "unconnected-(P1-PadK19)") (class "Default")
      (node (ref "P1") (pin "K19") (pinfunction "K19_K19") (pintype "passive"))
    )
    (net (code "272") (name "unconnected-(P1-PadK20)") (class "Default")
      (node (ref "P1") (pin "K20") (pinfunction "K20_K20") (pintype "passive"))
    )
    (net (code "273") (name "unconnected-(P1-PadK22)") (class "Default")
      (node (ref "P1") (pin "K22") (pinfunction "K22_K22") (pintype "passive"))
    )
    (net (code "274") (name "unconnected-(P1-PadK23)") (class "Default")
      (node (ref "P1") (pin "K23") (pinfunction "K23_K23") (pintype "passive"))
    )
    (net (code "275") (name "unconnected-(P1-PadK25)") (class "Default")
      (node (ref "P1") (pin "K25") (pinfunction "K25_K25") (pintype "passive"))
    )
    (net (code "276") (name "unconnected-(P1-PadK26)") (class "Default")
      (node (ref "P1") (pin "K26") (pinfunction "K26_K26") (pintype "passive"))
    )
    (net (code "277") (name "unconnected-(P1-PadK28)") (class "Default")
      (node (ref "P1") (pin "K28") (pinfunction "K28_K28") (pintype "passive"))
    )
    (net (code "278") (name "unconnected-(P1-PadK29)") (class "Default")
      (node (ref "P1") (pin "K29") (pinfunction "K29_K29") (pintype "passive"))
    )
    (net (code "279") (name "unconnected-(P1-PadK31)") (class "Default")
      (node (ref "P1") (pin "K31") (pinfunction "K31_K31") (pintype "passive"))
    )
    (net (code "280") (name "unconnected-(P1-PadK32)") (class "Default")
      (node (ref "P1") (pin "K32") (pinfunction "K32_K32") (pintype "passive"))
    )
    (net (code "281") (name "unconnected-(P1-PadK34)") (class "Default")
      (node (ref "P1") (pin "K34") (pinfunction "K34_K34") (pintype "passive"))
    )
    (net (code "282") (name "unconnected-(P1-PadK35)") (class "Default")
      (node (ref "P1") (pin "K35") (pinfunction "K35_K35") (pintype "passive"))
    )
    (net (code "283") (name "unconnected-(P1-PadK37)") (class "Default")
      (node (ref "P1") (pin "K37") (pinfunction "K37_K37") (pintype "passive"))
    )
    (net (code "284") (name "unconnected-(P1-PadK38)") (class "Default")
      (node (ref "P1") (pin "K38") (pinfunction "K38_K38") (pintype "passive"))
    )
    (net (code "285") (name "unconnected-(P1-PadK40)") (class "Default")
      (node (ref "P1") (pin "K40") (pinfunction "K40_K40") (pintype "passive"))
    )
  )
)
